# DummyLoad.net
KiCad netlist of a schematic drawn in EAGLE
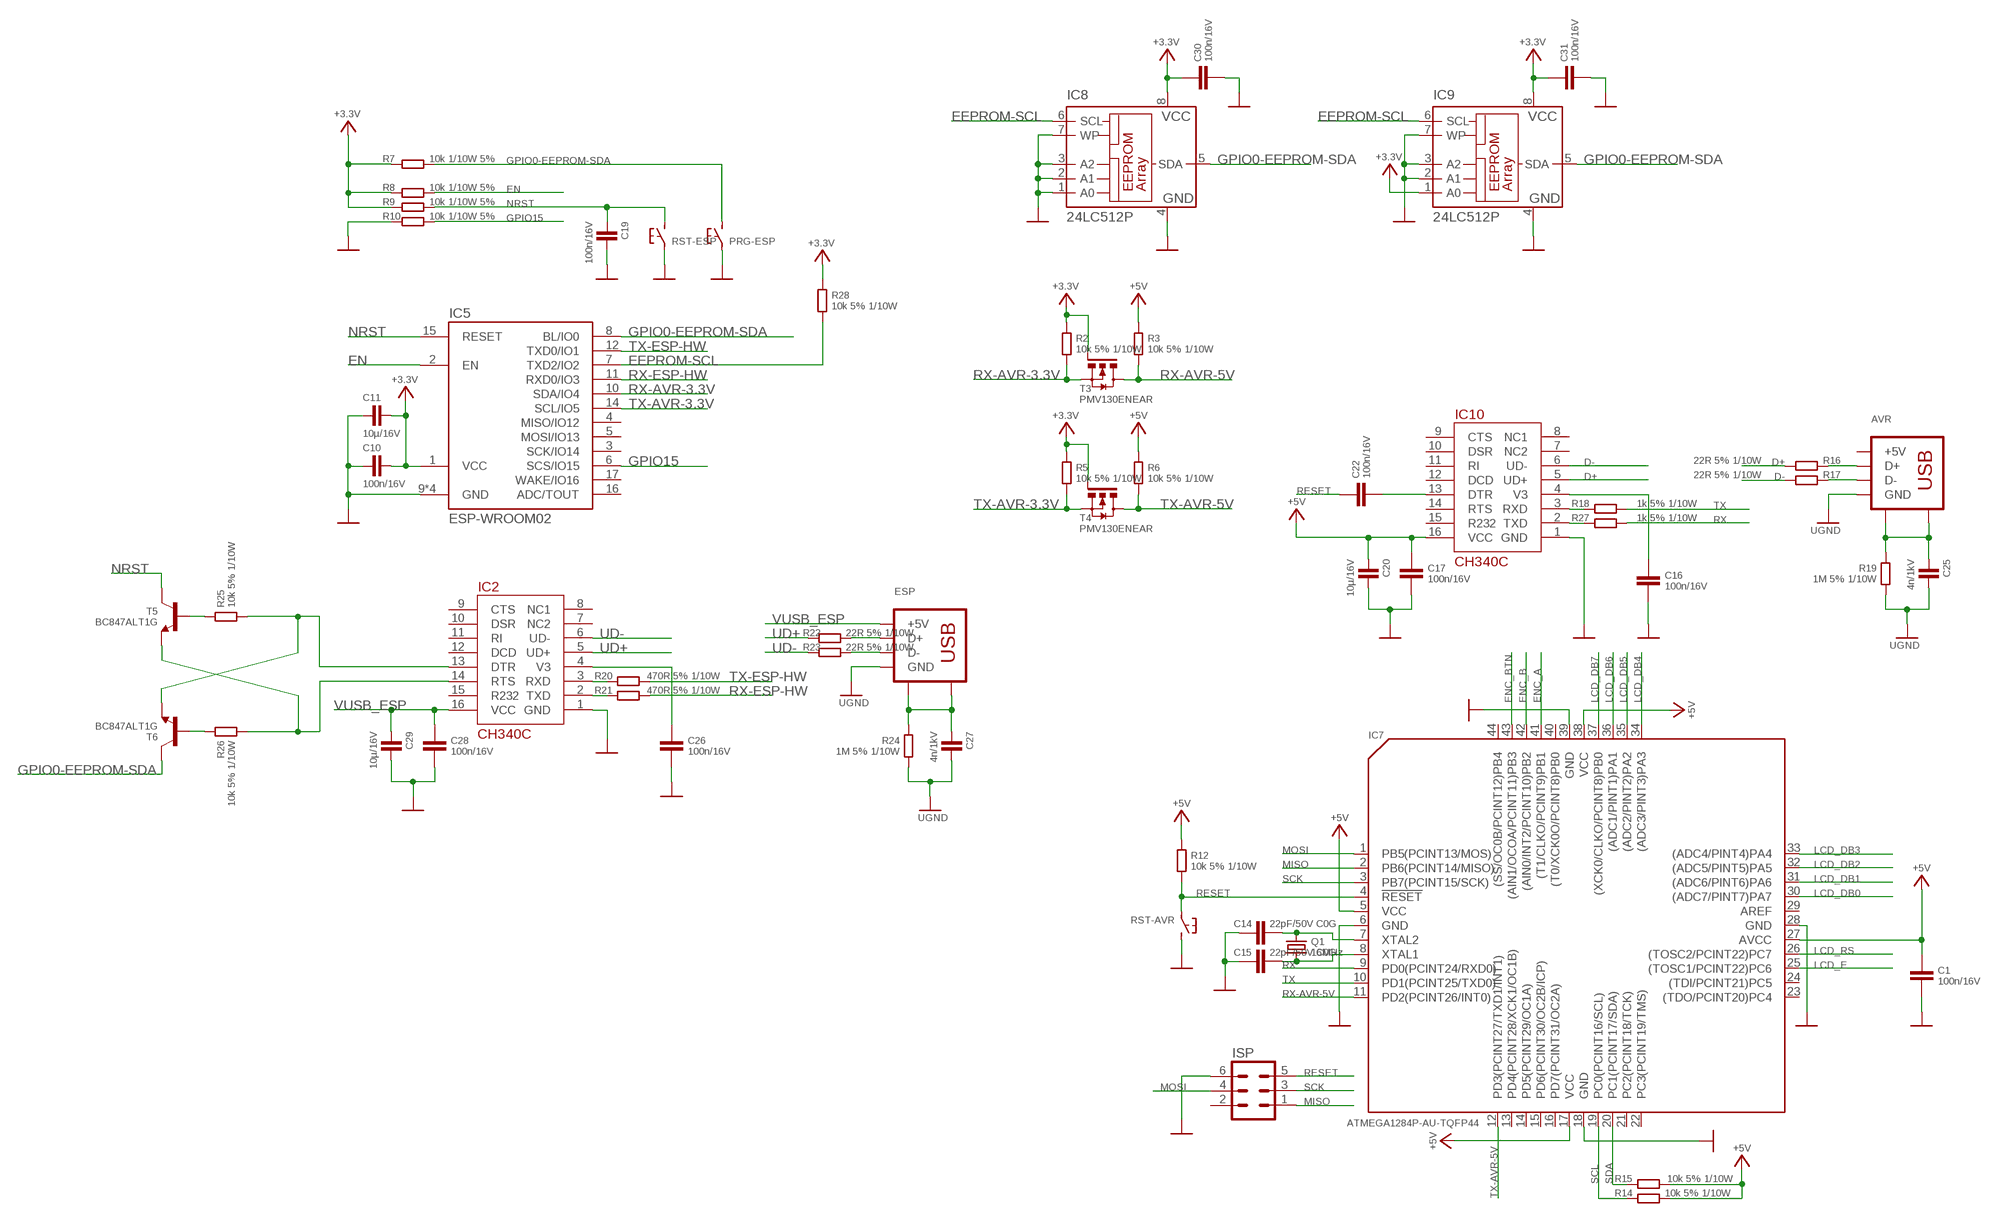
[diagram p0: schematic, sheet 1, part 1 of 2]
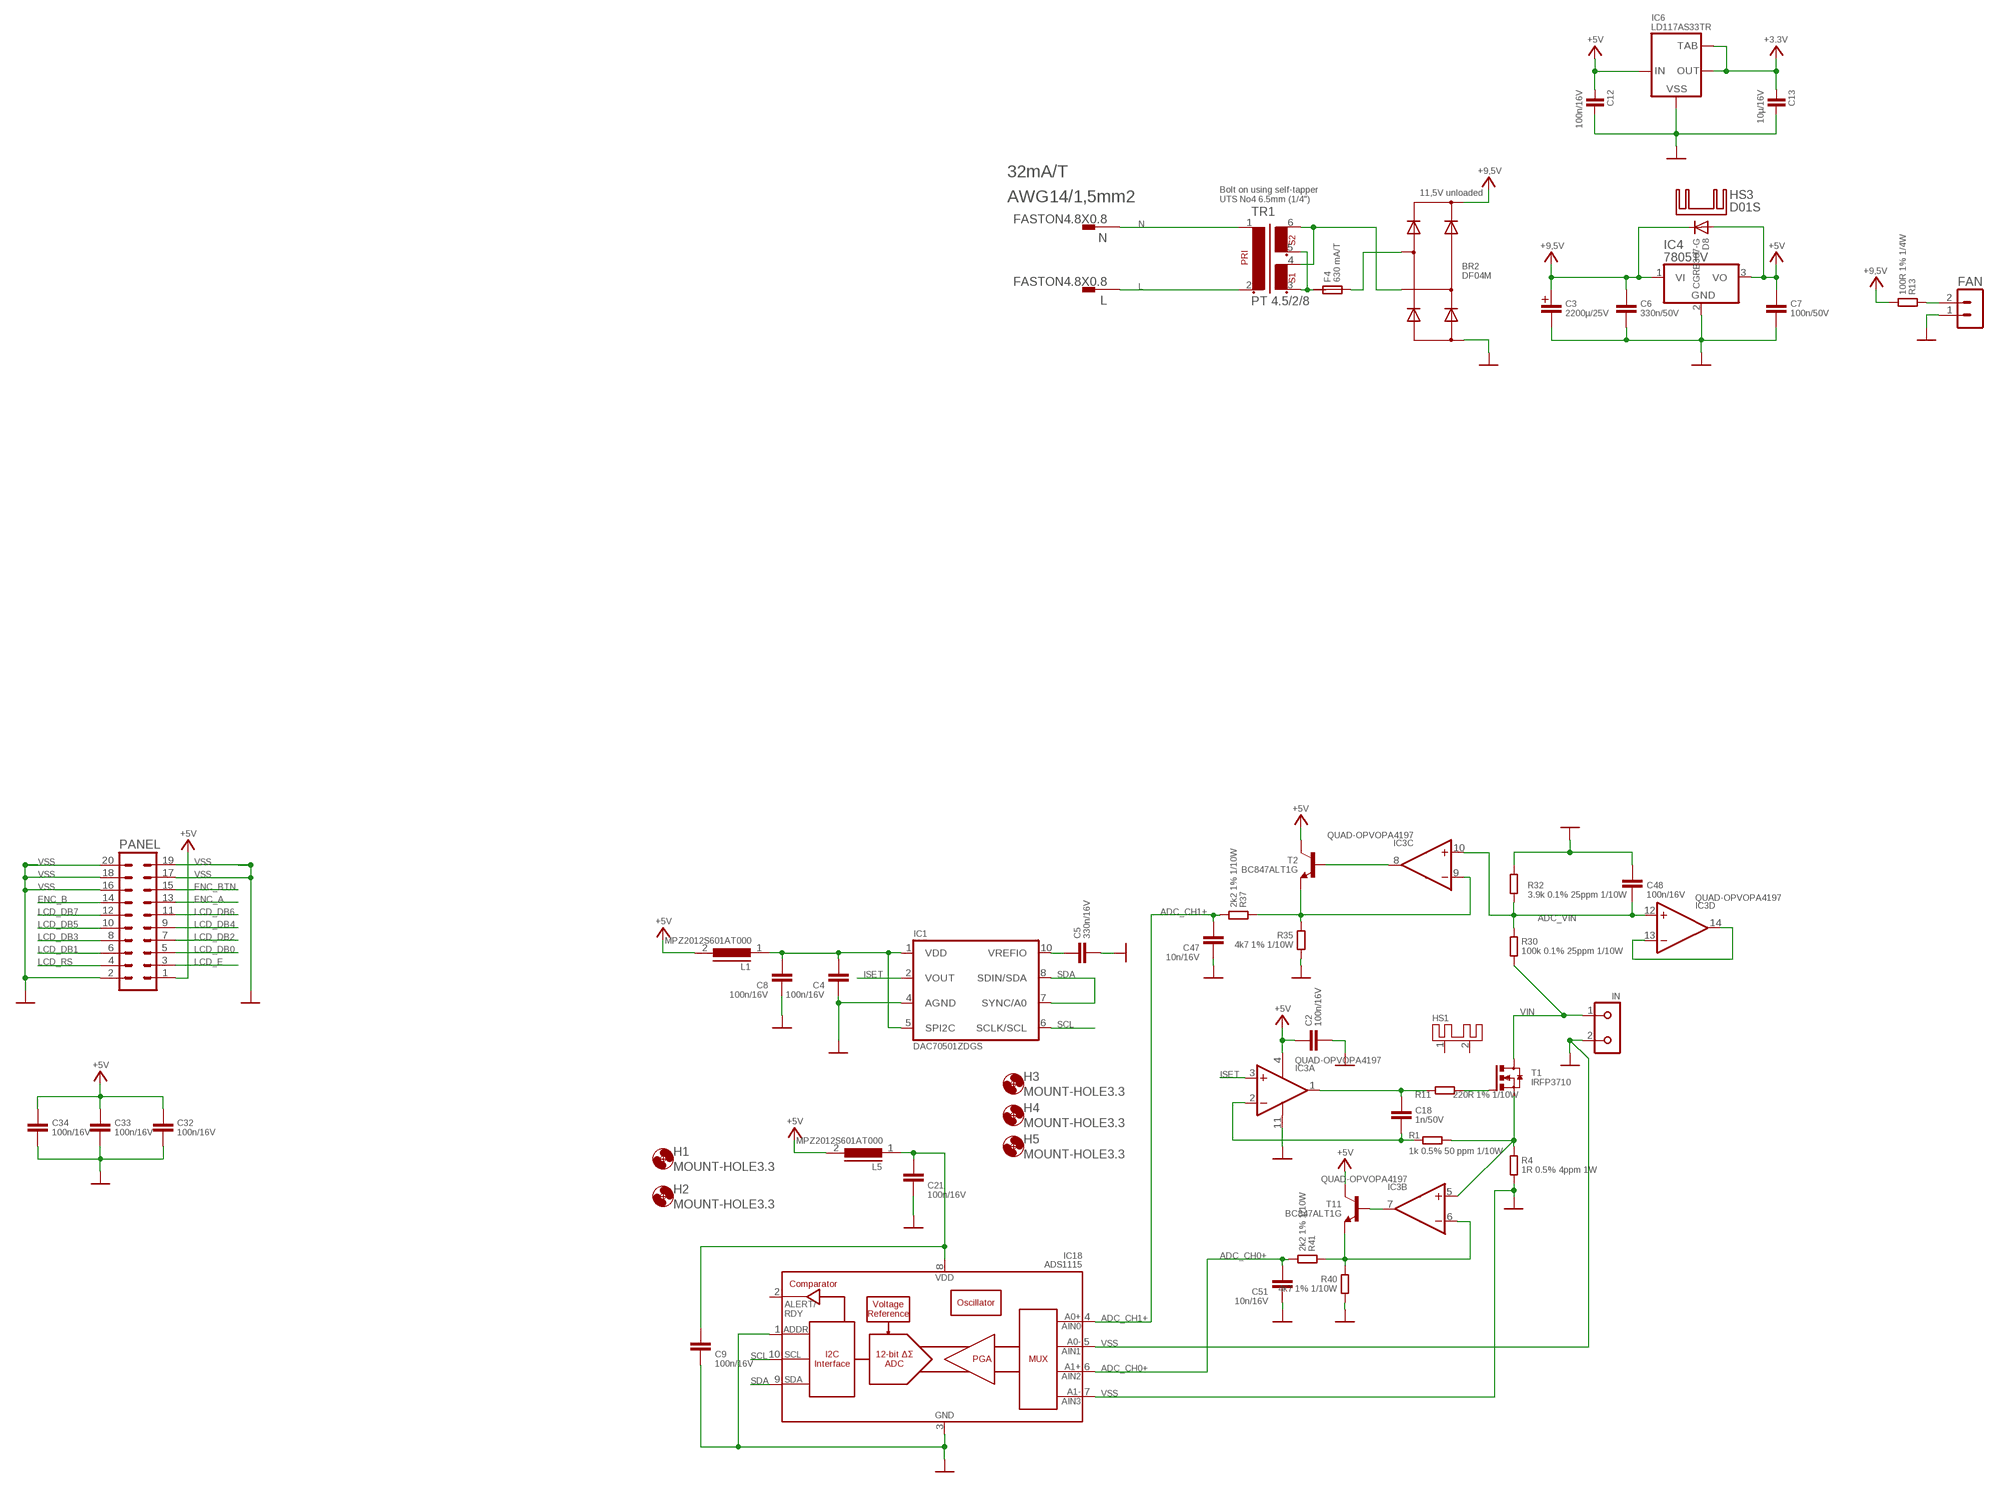
[diagram p1: schematic, sheet 1, part 2 of 2]

(export (version "E")
  (design (tool "Eeschema 10.0.6"))
  (components
    (comp (ref "AVR")
      (value "USBUSB-B")
      (footprint "eagle-import:USB-B")
      (libsource (lib "eagle-import") (part "USBUSB-B"))
    )
    (comp (ref "BR2")
      (value "DF04M")
      (footprint "eagle-import:BR-DIL2")
      (libsource (lib "eagle-import") (part "BRDIL2"))
    )
    (comp (ref "C1")
      (value "100n/16V")
      (footprint "eagle-import:0805")
      (libsource (lib "eagle-import") (part "CC/0805"))
    )
    (comp (ref "C2")
      (value "100n/16V")
      (footprint "eagle-import:0805")
      (libsource (lib "eagle-import") (part "CC/0805"))
    )
    (comp (ref "C3")
      (value "2200µ/25V")
      (footprint "eagle-import:C+_5_12.5")
      (libsource (lib "eagle-import") (part "C+5/12.5"))
    )
    (comp (ref "C4")
      (value "100n/16V")
      (footprint "eagle-import:0805")
      (libsource (lib "eagle-import") (part "CC/0805"))
    )
    (comp (ref "C5")
      (value "330n/16V")
      (footprint "eagle-import:0805")
      (libsource (lib "eagle-import") (part "CC/0805"))
    )
    (comp (ref "C6")
      (value "330n/50V")
      (footprint "eagle-import:0805")
      (libsource (lib "eagle-import") (part "CC/0805"))
    )
    (comp (ref "C7")
      (value "100n/50V")
      (footprint "eagle-import:0805")
      (libsource (lib "eagle-import") (part "CC/0805"))
    )
    (comp (ref "C8")
      (value "100n/16V")
      (footprint "eagle-import:0805")
      (libsource (lib "eagle-import") (part "CC/0805"))
    )
    (comp (ref "C9")
      (value "100n/16V")
      (footprint "eagle-import:0805")
      (libsource (lib "eagle-import") (part "CC/0805"))
    )
    (comp (ref "C10")
      (value "100n/16V")
      (footprint "eagle-import:C0805")
      (libsource (lib "eagle-import") (part "CAPACITOR-0805"))
    )
    (comp (ref "C11")
      (value "10µ/16V")
      (footprint "eagle-import:C1210")
      (libsource (lib "eagle-import") (part "CAPACITOR-1210"))
    )
    (comp (ref "C12")
      (value "100n/16V")
      (footprint "eagle-import:C0805")
      (libsource (lib "eagle-import") (part "CAPACITOR-0805"))
    )
    (comp (ref "C13")
      (value "10µ/16V")
      (footprint "eagle-import:C1210")
      (libsource (lib "eagle-import") (part "CAPACITOR-1210"))
    )
    (comp (ref "C14")
      (value "22pF/50V C0G")
      (footprint "eagle-import:0805")
      (libsource (lib "eagle-import") (part "CC/0805"))
    )
    (comp (ref "C15")
      (value "22pF/50V C0G")
      (footprint "eagle-import:0805")
      (libsource (lib "eagle-import") (part "CC/0805"))
    )
    (comp (ref "C16")
      (value "100n/16V")
      (footprint "eagle-import:0805")
      (libsource (lib "eagle-import") (part "CC/0805"))
    )
    (comp (ref "C17")
      (value "100n/16V")
      (footprint "eagle-import:0805")
      (libsource (lib "eagle-import") (part "CC/0805"))
    )
    (comp (ref "C18")
      (value "1n/50V")
      (footprint "eagle-import:0805")
      (libsource (lib "eagle-import") (part "CC/0805"))
    )
    (comp (ref "C19")
      (value "100n/16V")
      (footprint "eagle-import:C0805")
      (libsource (lib "eagle-import") (part "CAPACITOR-0805"))
    )
    (comp (ref "C20")
      (value "10µ/16V")
      (footprint "eagle-import:C1210")
      (libsource (lib "eagle-import") (part "CAPACITOR-1210"))
    )
    (comp (ref "C21")
      (value "100n/16V")
      (footprint "eagle-import:0805")
      (libsource (lib "eagle-import") (part "CC/0805"))
    )
    (comp (ref "C22")
      (value "100n/16V")
      (footprint "eagle-import:0805")
      (libsource (lib "eagle-import") (part "CC/0805"))
    )
    (comp (ref "C25")
      (value "4n/1kV")
      (footprint "eagle-import:C1206")
      (libsource (lib "eagle-import") (part "CAPACITOR-1206"))
    )
    (comp (ref "C26")
      (value "100n/16V")
      (footprint "eagle-import:0805")
      (libsource (lib "eagle-import") (part "CC/0805"))
    )
    (comp (ref "C27")
      (value "4n/1kV")
      (footprint "eagle-import:C1206")
      (libsource (lib "eagle-import") (part "CAPACITOR-1206"))
    )
    (comp (ref "C28")
      (value "100n/16V")
      (footprint "eagle-import:0805")
      (libsource (lib "eagle-import") (part "CC/0805"))
    )
    (comp (ref "C29")
      (value "10µ/16V")
      (footprint "eagle-import:C1210")
      (libsource (lib "eagle-import") (part "CAPACITOR-1210"))
    )
    (comp (ref "C30")
      (value "100n/16V")
      (footprint "eagle-import:0805")
      (libsource (lib "eagle-import") (part "CC/0805"))
    )
    (comp (ref "C31")
      (value "100n/16V")
      (footprint "eagle-import:0805")
      (libsource (lib "eagle-import") (part "CC/0805"))
    )
    (comp (ref "C32")
      (value "100n/16V")
      (footprint "eagle-import:0805")
      (libsource (lib "eagle-import") (part "CC/0805"))
    )
    (comp (ref "C33")
      (value "100n/16V")
      (footprint "eagle-import:0805")
      (libsource (lib "eagle-import") (part "CC/0805"))
    )
    (comp (ref "C34")
      (value "100n/16V")
      (footprint "eagle-import:0805")
      (libsource (lib "eagle-import") (part "CC/0805"))
    )
    (comp (ref "C47")
      (value "10n/16V")
      (footprint "eagle-import:0805")
      (libsource (lib "eagle-import") (part "CC/0805"))
    )
    (comp (ref "C48")
      (value "100n/16V")
      (footprint "eagle-import:0805")
      (libsource (lib "eagle-import") (part "CC/0805"))
    )
    (comp (ref "C51")
      (value "10n/16V")
      (footprint "eagle-import:0805")
      (libsource (lib "eagle-import") (part "CC/0805"))
    )
    (comp (ref "D8")
      (value "CGRB307-G")
      (footprint "eagle-import:DO214AA-CGRB307-G")
      (libsource (lib "eagle-import") (part "DWIDE"))
    )
    (comp (ref "ESP")
      (value "USBUSB-B")
      (footprint "eagle-import:USB-B")
      (libsource (lib "eagle-import") (part "USBUSB-B"))
    )
    (comp (ref "F4")
      (value "630 mA/T")
      (footprint "eagle-import:F5X20")
      (libsource (lib "eagle-import") (part "F5X20"))
    )
    (comp (ref "FAN")
      (value "JST-PH-2.0-2P")
      (footprint "eagle-import:JST-PH-2.0-2P")
      (libsource (lib "eagle-import") (part "JST-PH-2.0-2P"))
    )
    (comp (ref "H1")
      (value "MOUNT-HOLE3.3")
      (footprint "eagle-import:3,3")
      (libsource (lib "eagle-import") (part "MOUNT-HOLE3.3"))
    )
    (comp (ref "H2")
      (value "MOUNT-HOLE3.3")
      (footprint "eagle-import:3,3")
      (libsource (lib "eagle-import") (part "MOUNT-HOLE3.3"))
    )
    (comp (ref "H3")
      (value "MOUNT-HOLE3.3")
      (footprint "eagle-import:3,3")
      (libsource (lib "eagle-import") (part "MOUNT-HOLE3.3"))
    )
    (comp (ref "H4")
      (value "MOUNT-HOLE3.3")
      (footprint "eagle-import:3,3")
      (libsource (lib "eagle-import") (part "MOUNT-HOLE3.3"))
    )
    (comp (ref "H5")
      (value "MOUNT-HOLE3.3")
      (footprint "eagle-import:3,3")
      (libsource (lib "eagle-import") (part "MOUNT-HOLE3.3"))
    )
    (comp (ref "HS1")
      (value "HSCR201-50")
      (footprint "eagle-import:CR201-50")
      (libsource (lib "eagle-import") (part "HSCR201-50"))
    )
    (comp (ref "HS3")
      (value "D01S")
      (footprint "eagle-import:D01S")
      (libsource (lib "eagle-import") (part "D01S"))
    )
    (comp (ref "IC1")
      (value "DAC70501ZDGS")
      (footprint "eagle-import:VSSOP10")
      (libsource (lib "eagle-import") (part "DAC70501"))
    )
    (comp (ref "IC2")
      (value "CH340C")
      (footprint "eagle-import:SOP16")
      (libsource (lib "eagle-import") (part "CH340C"))
    )
    (comp (ref "IC3")
      (value "QUAD-OPVOPA4197")
      (footprint "eagle-import:SO14")
      (fields (field (name "OC_MOUSER") "595-OPA4197IDR"))
      (libsource (lib "eagle-import") (part "QUAD-OPVOPA4197"))
    )
    (comp (ref "IC4")
      (value "7805TV")
      (footprint "eagle-import:TO220V")
      (libsource (lib "eagle-import") (part "78TV05"))
    )
    (comp (ref "IC5")
      (value "ESP-WROOM02")
      (footprint "eagle-import:ESP-WROOM02")
      (libsource (lib "eagle-import") (part "ESP-WROOM02"))
    )
    (comp (ref "IC6")
      (value "LD117AS33TR")
      (footprint "eagle-import:SOT223")
      (libsource (lib "eagle-import") (part "LD117A?S33TR"))
    )
    (comp (ref "IC7")
      (value "ATMEGA1284P-AU-TQFP44")
      (footprint "eagle-import:TQFP44-0.8-9.6X9.6MM")
      (fields (field (name "MPN") "ATMEGA1284P-AU"))
      (libsource (lib "eagle-import") (part "MCU-ATMEGA1284P-AU(TQFP44)"))
    )
    (comp (ref "IC8")
      (value "24LC512P")
      (footprint "eagle-import:DIL08")
      (libsource (lib "eagle-import") (part "24P"))
    )
    (comp (ref "IC9")
      (value "24LC512P")
      (footprint "eagle-import:DIL08")
      (libsource (lib "eagle-import") (part "24P"))
    )
    (comp (ref "IC10")
      (value "CH340C")
      (footprint "eagle-import:SOP16")
      (libsource (lib "eagle-import") (part "CH340C"))
    )
    (comp (ref "IC18")
      (value "ADS1115")
      (footprint "eagle-import:VSSOP10")
      (libsource (lib "eagle-import") (part "ADS1015VSSOP10"))
    )
    (comp (ref "IN")
      (value "KL2691311500002")
      (footprint "eagle-import:KL2-691311500002")
      (libsource (lib "eagle-import") (part "KL2691311500002"))
    )
    (comp (ref "ISP")
      (value "ML6")
      (footprint "eagle-import:ML6")
      (libsource (lib "eagle-import") (part "ML6"))
    )
    (comp (ref "L")
      (value "FASTON4.8X0.8")
      (footprint "eagle-import:FASTON-4.8X0.8")
      (libsource (lib "eagle-import") (part "FASTON4.8X0.8"))
    )
    (comp (ref "L1")
      (value "MPZ2012S601AT000")
      (footprint "eagle-import:C0805K")
      (libsource (lib "eagle-import") (part "L0805"))
    )
    (comp (ref "L5")
      (value "MPZ2012S601AT000")
      (footprint "eagle-import:C0805K")
      (libsource (lib "eagle-import") (part "L0805"))
    )
    (comp (ref "N")
      (value "FASTON4.8X0.8")
      (footprint "eagle-import:FASTON-4.8X0.8")
      (libsource (lib "eagle-import") (part "FASTON4.8X0.8"))
    )
    (comp (ref "PANEL")
      (value "MA10-2")
      (footprint "eagle-import:MA10-2")
      (libsource (lib "eagle-import") (part "MA10-2"))
    )
    (comp (ref "PRG-ESP")
      (value "TS1B3F-10XX")
      (footprint "eagle-import:B3F-10XX")
      (libsource (lib "eagle-import") (part "TS1B3F-10XX"))
    )
    (comp (ref "Q1")
      (value "16MHz")
      (footprint "eagle-import:Q-5X3.2MM-TXC-7A.SERIES")
      (libsource (lib "eagle-import") (part "Q5X3.2MM-TXC-7A-SERIES"))
    )
    (comp (ref "R1")
      (value "1k 0.5% 50 ppm 1/10W")
      (footprint "eagle-import:C0805K")
      (libsource (lib "eagle-import") (part "R-SMD0805"))
    )
    (comp (ref "R2")
      (value "10k 5% 1/10W")
      (footprint "eagle-import:C0805K")
      (libsource (lib "eagle-import") (part "R-SMD0805"))
    )
    (comp (ref "R3")
      (value "10k 5% 1/10W")
      (footprint "eagle-import:C0805K")
      (libsource (lib "eagle-import") (part "R-SMD0805"))
    )
    (comp (ref "R4")
      (value "1R 0.5% 4ppm 1W")
      (footprint "eagle-import:R-SHUNT-VSR")
      (libsource (lib "eagle-import") (part "R-SHUNTVSR"))
    )
    (comp (ref "R5")
      (value "10k 5% 1/10W")
      (footprint "eagle-import:C0805K")
      (libsource (lib "eagle-import") (part "R-SMD0805"))
    )
    (comp (ref "R6")
      (value "10k 5% 1/10W")
      (footprint "eagle-import:C0805K")
      (libsource (lib "eagle-import") (part "R-SMD0805"))
    )
    (comp (ref "R7")
      (value "10k 1/10W 5%")
      (footprint "eagle-import:C0805K")
      (libsource (lib "eagle-import") (part "R-SMD0805"))
    )
    (comp (ref "R8")
      (value "10k 1/10W 5%")
      (footprint "eagle-import:C0805K")
      (libsource (lib "eagle-import") (part "R-SMD0805"))
    )
    (comp (ref "R9")
      (value "10k 1/10W 5%")
      (footprint "eagle-import:C0805K")
      (libsource (lib "eagle-import") (part "R-SMD0805"))
    )
    (comp (ref "R10")
      (value "10k 1/10W 5%")
      (footprint "eagle-import:C0805K")
      (libsource (lib "eagle-import") (part "R-SMD0805"))
    )
    (comp (ref "R11")
      (value "220R 1% 1/10W")
      (footprint "eagle-import:C0805K")
      (libsource (lib "eagle-import") (part "R-SMD0805"))
    )
    (comp (ref "R12")
      (value "10k 5% 1/10W")
      (footprint "eagle-import:C0805K")
      (libsource (lib "eagle-import") (part "R-SMD0805"))
    )
    (comp (ref "R13")
      (value "100R 1% 1/4W")
      (footprint "eagle-import:C0805K")
      (libsource (lib "eagle-import") (part "R-SMD0805"))
    )
    (comp (ref "R14")
      (value "10k 5% 1/10W")
      (footprint "eagle-import:C0805K")
      (libsource (lib "eagle-import") (part "R-SMD0805"))
    )
    (comp (ref "R15")
      (value "10k 5% 1/10W")
      (footprint "eagle-import:C0805K")
      (libsource (lib "eagle-import") (part "R-SMD0805"))
    )
    (comp (ref "R16")
      (value "22R 5% 1/10W")
      (footprint "eagle-import:C0805K")
      (libsource (lib "eagle-import") (part "R-SMD0805"))
    )
    (comp (ref "R17")
      (value "22R 5% 1/10W")
      (footprint "eagle-import:C0805K")
      (libsource (lib "eagle-import") (part "R-SMD0805"))
    )
    (comp (ref "R18")
      (value "1k 5% 1/10W")
      (footprint "eagle-import:C0805K")
      (libsource (lib "eagle-import") (part "R-SMD0805"))
    )
    (comp (ref "R19")
      (value "1M 5% 1/10W")
      (footprint "eagle-import:C0805K")
      (libsource (lib "eagle-import") (part "R-SMD0805"))
    )
    (comp (ref "R20")
      (value "470R 5% 1/10W")
      (footprint "eagle-import:C0805K")
      (libsource (lib "eagle-import") (part "R-SMD0805"))
    )
    (comp (ref "R21")
      (value "470R 5% 1/10W")
      (footprint "eagle-import:C0805K")
      (libsource (lib "eagle-import") (part "R-SMD0805"))
    )
    (comp (ref "R22")
      (value "22R 5% 1/10W")
      (footprint "eagle-import:C0805K")
      (libsource (lib "eagle-import") (part "R-SMD0805"))
    )
    (comp (ref "R23")
      (value "22R 5% 1/10W")
      (footprint "eagle-import:C0805K")
      (libsource (lib "eagle-import") (part "R-SMD0805"))
    )
    (comp (ref "R24")
      (value "1M 5% 1/10W")
      (footprint "eagle-import:C0805K")
      (libsource (lib "eagle-import") (part "R-SMD0805"))
    )
    (comp (ref "R25")
      (value "10k 5% 1/10W")
      (footprint "eagle-import:C0805K")
      (libsource (lib "eagle-import") (part "R-SMD0805"))
    )
    (comp (ref "R26")
      (value "10k 5% 1/10W")
      (footprint "eagle-import:C0805K")
      (libsource (lib "eagle-import") (part "R-SMD0805"))
    )
    (comp (ref "R27")
      (value "1k 5% 1/10W")
      (footprint "eagle-import:C0805K")
      (libsource (lib "eagle-import") (part "R-SMD0805"))
    )
    (comp (ref "R28")
      (value "10k 5% 1/10W")
      (footprint "eagle-import:C0805K")
      (libsource (lib "eagle-import") (part "R-SMD0805"))
    )
    (comp (ref "R30")
      (value "100k 0.1% 25ppm 1/10W")
      (footprint "eagle-import:C0805K")
      (libsource (lib "eagle-import") (part "R-SMD0805"))
    )
    (comp (ref "R32")
      (value "3.9k 0.1% 25ppm 1/10W")
      (footprint "eagle-import:C0805K")
      (libsource (lib "eagle-import") (part "R-SMD0805"))
    )
    (comp (ref "R35")
      (value "4k7 1% 1/10W")
      (footprint "eagle-import:C0805K")
      (libsource (lib "eagle-import") (part "R-SMD0805"))
    )
    (comp (ref "R37")
      (value "2k2 1% 1/10W")
      (footprint "eagle-import:C0805K")
      (libsource (lib "eagle-import") (part "R-SMD0805"))
    )
    (comp (ref "R40")
      (value "4k7 1% 1/10W")
      (footprint "eagle-import:C0805K")
      (libsource (lib "eagle-import") (part "R-SMD0805"))
    )
    (comp (ref "R41")
      (value "2k2 1% 1/10W")
      (footprint "eagle-import:C0805K")
      (libsource (lib "eagle-import") (part "R-SMD0805"))
    )
    (comp (ref "RST-AVR")
      (value "TS1B3F-10XX")
      (footprint "eagle-import:B3F-10XX")
      (libsource (lib "eagle-import") (part "TS1B3F-10XX"))
    )
    (comp (ref "RST-ESP")
      (value "TS1B3F-10XX")
      (footprint "eagle-import:B3F-10XX")
      (libsource (lib "eagle-import") (part "TS1B3F-10XX"))
    )
    (comp (ref "T1")
      (value "IRFP3710")
      (footprint "eagle-import:TOP3AV")
      (libsource (lib "eagle-import") (part "T-NMOSTO247"))
    )
    (comp (ref "T2")
      (value "BC847ALT1G")
      (footprint "eagle-import:SOT23-BEC")
      (libsource (lib "eagle-import") (part "T-NPNSOT23-BEC"))
    )
    (comp (ref "T3")
      (value "PMV130ENEAR")
      (footprint "eagle-import:SOT23")
      (libsource (lib "eagle-import") (part "T-NMOSIRLML2502PBF"))
    )
    (comp (ref "T4")
      (value "PMV130ENEAR")
      (footprint "eagle-import:SOT23")
      (libsource (lib "eagle-import") (part "T-NMOSIRLML2502PBF"))
    )
    (comp (ref "T5")
      (value "BC847ALT1G")
      (footprint "eagle-import:SOT23-BEC")
      (libsource (lib "eagle-import") (part "T-NPNSOT23-BEC"))
    )
    (comp (ref "T6")
      (value "BC847ALT1G")
      (footprint "eagle-import:SOT23-BEC")
      (libsource (lib "eagle-import") (part "T-NPNSOT23-BEC"))
    )
    (comp (ref "T11")
      (value "BC847ALT1G")
      (footprint "eagle-import:SOT23-BEC")
      (libsource (lib "eagle-import") (part "T-NPNSOT23-BEC"))
    )
    (comp (ref "TR1")
      (value "PT 4.5/2/8")
      (footprint "eagle-import:PT_4,5_2_..")
      (libsource (lib "eagle-import") (part "PT4,5/2/.."))
    )
  )
  (nets
    (net (code "1") (name "+3.3V") (class "Default")
      (node (ref "C10") (pin "2") (pinfunction "2_2") (pintype "passive"))
      (node (ref "C11") (pin "2") (pinfunction "2_2") (pintype "passive"))
      (node (ref "C13") (pin "1") (pinfunction "1_1") (pintype "passive"))
      (node (ref "C30") (pin "1") (pinfunction "1_1") (pintype "passive"))
      (node (ref "C31") (pin "1") (pinfunction "1_1") (pintype "passive"))
      (node (ref "IC5") (pin "1") (pinfunction "VCC_1") (pintype "power_in"))
      (node (ref "IC6") (pin "2") (pinfunction "OUT_2") (pintype "passive"))
      (node (ref "IC6") (pin "4") (pinfunction "OUT1_4") (pintype "passive"))
      (node (ref "IC8") (pin "8") (pinfunction "VCC_8") (pintype "power_in"))
      (node (ref "IC9") (pin "1") (pinfunction "A0_1") (pintype "input"))
      (node (ref "IC9") (pin "8") (pinfunction "VCC_8") (pintype "power_in"))
      (node (ref "R2") (pin "1") (pinfunction "1_1") (pintype "passive"))
      (node (ref "R28") (pin "1") (pinfunction "1_1") (pintype "passive"))
      (node (ref "R5") (pin "1") (pinfunction "1_1") (pintype "passive"))
      (node (ref "R7") (pin "1") (pinfunction "1_1") (pintype "passive"))
      (node (ref "R8") (pin "1") (pinfunction "1_1") (pintype "passive"))
      (node (ref "R9") (pin "1") (pinfunction "1_1") (pintype "passive"))
      (node (ref "T3") (pin "1") (pinfunction "G_1") (pintype "passive"))
      (node (ref "T4") (pin "1") (pinfunction "G_1") (pintype "passive"))
    )
    (net (code "2") (name "+5V") (class "Default")
      (node (ref "C1") (pin "1") (pinfunction "1_1") (pintype "passive"))
      (node (ref "C12") (pin "1") (pinfunction "1_1") (pintype "passive"))
      (node (ref "C17") (pin "1") (pinfunction "1_1") (pintype "passive"))
      (node (ref "C2") (pin "1") (pinfunction "1_1") (pintype "passive"))
      (node (ref "C20") (pin "1") (pinfunction "1_1") (pintype "passive"))
      (node (ref "C32") (pin "1") (pinfunction "1_1") (pintype "passive"))
      (node (ref "C33") (pin "1") (pinfunction "1_1") (pintype "passive"))
      (node (ref "C34") (pin "1") (pinfunction "1_1") (pintype "passive"))
      (node (ref "C7") (pin "1") (pinfunction "1_1") (pintype "passive"))
      (node (ref "D8") (pin "A") (pinfunction "A_A") (pintype "passive"))
      (node (ref "IC10") (pin "16") (pinfunction "VCC_16") (pintype "power_in"))
      (node (ref "IC3") (pin "4") (pinfunction "V+_4") (pintype "power_in"))
      (node (ref "IC4") (pin "3") (pinfunction "VO_3") (pintype "passive"))
      (node (ref "IC6") (pin "3") (pinfunction "IN_3") (pintype "input"))
      (node (ref "IC7") (pin "17") (pinfunction "VCC_17") (pintype "bidirectional"))
      (node (ref "IC7") (pin "27") (pinfunction "AVCC_27") (pintype "bidirectional"))
      (node (ref "IC7") (pin "38") (pinfunction "VCC_38") (pintype "bidirectional"))
      (node (ref "IC7") (pin "5") (pinfunction "VCC_5") (pintype "bidirectional"))
      (node (ref "L1") (pin "2") (pinfunction "2_2") (pintype "passive"))
      (node (ref "L5") (pin "2") (pinfunction "2_2") (pintype "passive"))
      (node (ref "PANEL") (pin "1") (pinfunction "1_1") (pintype "passive"))
      (node (ref "R12") (pin "1") (pinfunction "1_1") (pintype "passive"))
      (node (ref "R14") (pin "2") (pinfunction "2_2") (pintype "passive"))
      (node (ref "R15") (pin "2") (pinfunction "2_2") (pintype "passive"))
      (node (ref "R3") (pin "1") (pinfunction "1_1") (pintype "passive"))
      (node (ref "R6") (pin "1") (pinfunction "1_1") (pintype "passive"))
      (node (ref "T11") (pin "C") (pinfunction "C_C") (pintype "passive"))
      (node (ref "T2") (pin "C") (pinfunction "C_C") (pintype "passive"))
    )
    (net (code "3") (name "+9,5V") (class "Default")
      (node (ref "BR2") (pin "DC+") (pinfunction "DC+_DC+") (pintype "passive"))
      (node (ref "C3") (pin "+") (pinfunction "+_+") (pintype "passive"))
      (node (ref "C6") (pin "1") (pinfunction "1_1") (pintype "passive"))
      (node (ref "D8") (pin "C") (pinfunction "C_C") (pintype "passive"))
      (node (ref "IC4") (pin "1") (pinfunction "VI_1") (pintype "input"))
      (node (ref "R13") (pin "2") (pinfunction "2_2") (pintype "passive"))
    )
    (net (code "4") (name "/ADC_CH0+") (class "Default")
      (node (ref "C51") (pin "1") (pinfunction "1_1") (pintype "passive"))
      (node (ref "IC18") (pin "6") (pinfunction "AIN2_6") (pintype "bidirectional"))
      (node (ref "R41") (pin "2") (pinfunction "2_2") (pintype "passive"))
    )
    (net (code "5") (name "/ADC_CH1+") (class "Default")
      (node (ref "C47") (pin "1") (pinfunction "1_1") (pintype "passive"))
      (node (ref "IC18") (pin "4") (pinfunction "AIN0_4") (pintype "bidirectional"))
      (node (ref "R37") (pin "2") (pinfunction "2_2") (pintype "passive"))
    )
    (net (code "6") (name "/ADC_VIN") (class "Default")
      (node (ref "C48") (pin "2") (pinfunction "2_2") (pintype "passive"))
      (node (ref "IC3") (pin "10") (pinfunction "+IN_10") (pintype "input"))
      (node (ref "IC3") (pin "12") (pinfunction "+IN_12") (pintype "input"))
      (node (ref "R30") (pin "1") (pinfunction "1_1") (pintype "passive"))
      (node (ref "R32") (pin "2") (pinfunction "2_2") (pintype "passive"))
    )
    (net (code "7") (name "/D+") (class "Default")
      (node (ref "IC10") (pin "5") (pinfunction "UD+_5") (pintype "bidirectional"))
      (node (ref "R16") (pin "1") (pinfunction "1_1") (pintype "passive"))
    )
    (net (code "8") (name "/D-") (class "Default")
      (node (ref "IC10") (pin "6") (pinfunction "UD-_6") (pintype "bidirectional"))
      (node (ref "R17") (pin "1") (pinfunction "1_1") (pintype "passive"))
    )
    (net (code "9") (name "/EEPROM-SCL") (class "Default")
      (node (ref "IC5") (pin "7") (pinfunction "TXD2/IO2_7") (pintype "bidirectional"))
      (node (ref "IC8") (pin "6") (pinfunction "SCL_6") (pintype "input"))
      (node (ref "IC9") (pin "6") (pinfunction "SCL_6") (pintype "input"))
      (node (ref "R28") (pin "2") (pinfunction "2_2") (pintype "passive"))
    )
    (net (code "10") (name "/EN") (class "Default")
      (node (ref "IC5") (pin "2") (pinfunction "EN_2") (pintype "bidirectional"))
      (node (ref "R8") (pin "2") (pinfunction "2_2") (pintype "passive"))
    )
    (net (code "11") (name "/ENC_A") (class "Default")
      (node (ref "IC7") (pin "41") (pinfunction "(T1/CLKO/PCINT9)PB1_41") (pintype "bidirectional"))
      (node (ref "PANEL") (pin "13") (pinfunction "13_13") (pintype "passive"))
    )
    (net (code "12") (name "/ENC_B") (class "Default")
      (node (ref "IC7") (pin "42") (pinfunction "(AIN0/INT2/PCINT10)PB2_42") (pintype "bidirectional"))
      (node (ref "PANEL") (pin "14") (pinfunction "14_14") (pintype "passive"))
    )
    (net (code "13") (name "/ENC_BTN") (class "Default")
      (node (ref "IC7") (pin "43") (pinfunction "(AIN1/OCOA/PCINT11)PB3_43") (pintype "bidirectional"))
      (node (ref "PANEL") (pin "15") (pinfunction "15_15") (pintype "passive"))
    )
    (net (code "14") (name "/GPIO0-EEPROM-SDA") (class "Default")
      (node (ref "IC5") (pin "8") (pinfunction "BL/IO0_8") (pintype "bidirectional"))
      (node (ref "IC8") (pin "5") (pinfunction "SDA_5") (pintype "bidirectional"))
      (node (ref "IC9") (pin "5") (pinfunction "SDA_5") (pintype "bidirectional"))
      (node (ref "PRG-ESP") (pin "3") (pinfunction "2_3") (pintype "passive"))
      (node (ref "R7") (pin "2") (pinfunction "2_2") (pintype "passive"))
      (node (ref "T6") (pin "C") (pinfunction "C_C") (pintype "passive"))
    )
    (net (code "15") (name "/GPIO15") (class "Default")
      (node (ref "IC5") (pin "6") (pinfunction "SCS/IO15_6") (pintype "bidirectional"))
      (node (ref "R10") (pin "2") (pinfunction "2_2") (pintype "passive"))
    )
    (net (code "16") (name "/ISET") (class "Default")
      (node (ref "IC1") (pin "2") (pinfunction "VOUT_2") (pintype "output"))
      (node (ref "IC3") (pin "3") (pinfunction "+IN_3") (pintype "input"))
    )
    (net (code "17") (name "/L") (class "Default")
      (node (ref "L") (pin "A1") (pinfunction "1_A1") (pintype "passive"))
      (node (ref "L") (pin "A2") (pinfunction "1_A2") (pintype "passive"))
      (node (ref "TR1") (pin "2") (pinfunction "2_2") (pintype "passive"))
    )
    (net (code "18") (name "/LCD_DB0") (class "Default")
      (node (ref "IC7") (pin "30") (pinfunction "(ADC7/PINT7)PA7_30") (pintype "bidirectional"))
      (node (ref "PANEL") (pin "5") (pinfunction "5_5") (pintype "passive"))
    )
    (net (code "19") (name "/LCD_DB1") (class "Default")
      (node (ref "IC7") (pin "31") (pinfunction "(ADC6/PINT6)PA6_31") (pintype "bidirectional"))
      (node (ref "PANEL") (pin "6") (pinfunction "6_6") (pintype "passive"))
    )
    (net (code "20") (name "/LCD_DB2") (class "Default")
      (node (ref "IC7") (pin "32") (pinfunction "(ADC5/PINT5)PA5_32") (pintype "bidirectional"))
      (node (ref "PANEL") (pin "7") (pinfunction "7_7") (pintype "passive"))
    )
    (net (code "21") (name "/LCD_DB3") (class "Default")
      (node (ref "IC7") (pin "33") (pinfunction "(ADC4/PINT4)PA4_33") (pintype "bidirectional"))
      (node (ref "PANEL") (pin "8") (pinfunction "8_8") (pintype "passive"))
    )
    (net (code "22") (name "/LCD_DB4") (class "Default")
      (node (ref "IC7") (pin "34") (pinfunction "(ADC3/PINT3)PA3_34") (pintype "bidirectional"))
      (node (ref "PANEL") (pin "9") (pinfunction "9_9") (pintype "passive"))
    )
    (net (code "23") (name "/LCD_DB5") (class "Default")
      (node (ref "IC7") (pin "35") (pinfunction "(ADC2/PINT2)PA2_35") (pintype "bidirectional"))
      (node (ref "PANEL") (pin "10") (pinfunction "10_10") (pintype "passive"))
    )
    (net (code "24") (name "/LCD_DB6") (class "Default")
      (node (ref "IC7") (pin "36") (pinfunction "(ADC1/PINT1)PA1_36") (pintype "bidirectional"))
      (node (ref "PANEL") (pin "11") (pinfunction "11_11") (pintype "passive"))
    )
    (net (code "25") (name "/LCD_DB7") (class "Default")
      (node (ref "IC7") (pin "37") (pinfunction "(XCK0/CLKO/PCINT8)PB0_37") (pintype "bidirectional"))
      (node (ref "PANEL") (pin "12") (pinfunction "12_12") (pintype "passive"))
    )
    (net (code "26") (name "/LCD_E") (class "Default")
      (node (ref "IC7") (pin "25") (pinfunction "(TOSC1/PCINT22)PC6_25") (pintype "bidirectional"))
      (node (ref "PANEL") (pin "3") (pinfunction "3_3") (pintype "passive"))
    )
    (net (code "27") (name "/LCD_RS") (class "Default")
      (node (ref "IC7") (pin "26") (pinfunction "(TOSC2/PCINT22)PC7_26") (pintype "bidirectional"))
      (node (ref "PANEL") (pin "4") (pinfunction "4_4") (pintype "passive"))
    )
    (net (code "28") (name "/MISO") (class "Default")
      (node (ref "IC7") (pin "2") (pinfunction "PB6(PCINT14/MISO)_2") (pintype "bidirectional"))
      (node (ref "ISP") (pin "1") (pinfunction "1_1") (pintype "passive"))
    )
    (net (code "29") (name "/MOSI") (class "Default")
      (node (ref "IC7") (pin "1") (pinfunction "PB5(PCINT13/MOS)_1") (pintype "bidirectional"))
      (node (ref "ISP") (pin "4") (pinfunction "4_4") (pintype "passive"))
    )
    (net (code "30") (name "/N") (class "Default")
      (node (ref "N") (pin "A1") (pinfunction "1_A1") (pintype "passive"))
      (node (ref "N") (pin "A2") (pinfunction "1_A2") (pintype "passive"))
      (node (ref "TR1") (pin "1") (pinfunction "1_1") (pintype "passive"))
    )
    (net (code "31") (name "/NRST") (class "Default")
      (node (ref "C19") (pin "1") (pinfunction "1_1") (pintype "passive"))
      (node (ref "IC5") (pin "15") (pinfunction "RESET_15") (pintype "bidirectional"))
      (node (ref "R9") (pin "2") (pinfunction "2_2") (pintype "passive"))
      (node (ref "RST-ESP") (pin "3") (pinfunction "2_3") (pintype "passive"))
      (node (ref "T5") (pin "C") (pinfunction "C_C") (pintype "passive"))
    )
    (net (code "32") (name "/RESET") (class "Default")
      (node (ref "C22") (pin "1") (pinfunction "1_1") (pintype "passive"))
      (node (ref "IC7") (pin "4") (pinfunction "~{RESET}_4") (pintype "bidirectional"))
      (node (ref "ISP") (pin "5") (pinfunction "5_5") (pintype "passive"))
      (node (ref "R12") (pin "2") (pinfunction "2_2") (pintype "passive"))
      (node (ref "RST-AVR") (pin "1") (pinfunction "1_1") (pintype "passive"))
    )
    (net (code "33") (name "/RX") (class "Default")
      (node (ref "IC7") (pin "9") (pinfunction "PD0(PCINT24/RXD0)_9") (pintype "bidirectional"))
      (node (ref "R27") (pin "2") (pinfunction "2_2") (pintype "passive"))
    )
    (net (code "34") (name "/RX-AVR-3.3V") (class "Default")
      (node (ref "IC5") (pin "10") (pinfunction "SDA/IO4_10") (pintype "bidirectional"))
      (node (ref "R2") (pin "2") (pinfunction "2_2") (pintype "passive"))
      (node (ref "T3") (pin "2") (pinfunction "S_2") (pintype "passive"))
    )
    (net (code "35") (name "/RX-AVR-5V") (class "Default")
      (node (ref "IC7") (pin "11") (pinfunction "PD2(PCINT26/INT0)_11") (pintype "bidirectional"))
      (node (ref "R3") (pin "2") (pinfunction "2_2") (pintype "passive"))
      (node (ref "T3") (pin "3") (pinfunction "D_3") (pintype "passive"))
    )
    (net (code "36") (name "/RX-ESP-HW") (class "Default")
      (node (ref "IC5") (pin "11") (pinfunction "RXD0/IO3_11") (pintype "bidirectional"))
      (node (ref "R21") (pin "2") (pinfunction "2_2") (pintype "passive"))
    )
    (net (code "37") (name "/SCK") (class "Default")
      (node (ref "IC7") (pin "3") (pinfunction "PB7(PCINT15/SCK)_3") (pintype "bidirectional"))
      (node (ref "ISP") (pin "3") (pinfunction "3_3") (pintype "passive"))
    )
    (net (code "38") (name "/SCL") (class "Default")
      (node (ref "IC1") (pin "6") (pinfunction "SCLK/SCL_6") (pintype "input"))
      (node (ref "IC18") (pin "10") (pinfunction "SCL_10") (pintype "bidirectional"))
      (node (ref "IC7") (pin "19") (pinfunction "PC0(PCINT16/SCL)_19") (pintype "bidirectional"))
      (node (ref "R14") (pin "1") (pinfunction "1_1") (pintype "passive"))
    )
    (net (code "39") (name "/SDA") (class "Default")
      (node (ref "IC1") (pin "7") (pinfunction "SYNC/A0_7") (pintype "input"))
      (node (ref "IC1") (pin "8") (pinfunction "SDIN/SDA_8") (pintype "input"))
      (node (ref "IC18") (pin "9") (pinfunction "SDA_9") (pintype "bidirectional"))
      (node (ref "IC7") (pin "20") (pinfunction "PC1(PCINT17/SDA)_20") (pintype "bidirectional"))
      (node (ref "R15") (pin "1") (pinfunction "1_1") (pintype "passive"))
    )
    (net (code "40") (name "/TX") (class "Default")
      (node (ref "IC7") (pin "10") (pinfunction "PD1(PCINT25/TXD0)_10") (pintype "bidirectional"))
      (node (ref "R18") (pin "2") (pinfunction "2_2") (pintype "passive"))
    )
    (net (code "41") (name "/TX-AVR-3.3V") (class "Default")
      (node (ref "IC5") (pin "14") (pinfunction "SCL/IO5_14") (pintype "bidirectional"))
      (node (ref "R5") (pin "2") (pinfunction "2_2") (pintype "passive"))
      (node (ref "T4") (pin "2") (pinfunction "S_2") (pintype "passive"))
    )
    (net (code "42") (name "/TX-AVR-5V") (class "Default")
      (node (ref "IC7") (pin "12") (pinfunction "PD3(PCINT27/TXD1/INT1)_12") (pintype "bidirectional"))
      (node (ref "R6") (pin "2") (pinfunction "2_2") (pintype "passive"))
      (node (ref "T4") (pin "3") (pinfunction "D_3") (pintype "passive"))
    )
    (net (code "43") (name "/TX-ESP-HW") (class "Default")
      (node (ref "IC5") (pin "12") (pinfunction "TXD0/IO1_12") (pintype "bidirectional"))
      (node (ref "R20") (pin "2") (pinfunction "2_2") (pintype "passive"))
    )
    (net (code "44") (name "/UD+") (class "Default")
      (node (ref "IC2") (pin "5") (pinfunction "UD+_5") (pintype "bidirectional"))
      (node (ref "R22") (pin "1") (pinfunction "1_1") (pintype "passive"))
    )
    (net (code "45") (name "/UD-") (class "Default")
      (node (ref "IC2") (pin "6") (pinfunction "UD-_6") (pintype "bidirectional"))
      (node (ref "R23") (pin "1") (pinfunction "1_1") (pintype "passive"))
    )
    (net (code "46") (name "/VIN") (class "Default")
      (node (ref "IN") (pin "1") (pinfunction "1_1") (pintype "passive"))
      (node (ref "R30") (pin "2") (pinfunction "2_2") (pintype "passive"))
      (node (ref "T1") (pin "C") (pinfunction "D_C") (pintype "passive"))
    )
    (net (code "47") (name "/VUSB_ESP") (class "Default")
      (node (ref "C28") (pin "1") (pinfunction "1_1") (pintype "passive"))
      (node (ref "C29") (pin "1") (pinfunction "1_1") (pintype "passive"))
      (node (ref "ESP") (pin "+5V") (pinfunction "+5V_+5V") (pintype "passive"))
      (node (ref "IC2") (pin "16") (pinfunction "VCC_16") (pintype "power_in"))
    )
    (net (code "48") (name "Net-(AVR-PadD+)") (class "Default")
      (node (ref "AVR") (pin "D+") (pinfunction "D+_D+") (pintype "bidirectional"))
      (node (ref "R16") (pin "2") (pinfunction "2_2") (pintype "passive"))
    )
    (net (code "49") (name "Net-(AVR-PadD-)") (class "Default")
      (node (ref "AVR") (pin "D-") (pinfunction "D-_D-") (pintype "bidirectional"))
      (node (ref "R17") (pin "2") (pinfunction "2_2") (pintype "passive"))
    )
    (net (code "50") (name "Net-(AVR-PadSH1)") (class "Default")
      (node (ref "AVR") (pin "SH1") (pinfunction "SH1_SH1") (pintype "passive"))
      (node (ref "AVR") (pin "SH2") (pinfunction "SH2_SH2") (pintype "passive"))
      (node (ref "C25") (pin "1") (pinfunction "1_1") (pintype "passive"))
      (node (ref "R19") (pin "1") (pinfunction "1_1") (pintype "passive"))
    )
    (net (code "51") (name "Net-(BR2-PadAC1)") (class "Default")
      (node (ref "BR2") (pin "AC1") (pinfunction "AC1_AC1") (pintype "passive"))
      (node (ref "F4") (pin "3") (pinfunction "2_3") (pintype "passive"))
      (node (ref "F4") (pin "4") (pinfunction "2_4") (pintype "passive"))
    )
    (net (code "52") (name "Net-(BR2-PadAC2)") (class "Default")
      (node (ref "BR2") (pin "AC2") (pinfunction "AC2_AC2") (pintype "passive"))
      (node (ref "TR1") (pin "4") (pinfunction "4_4") (pintype "passive"))
      (node (ref "TR1") (pin "6") (pinfunction "6_6") (pintype "passive"))
    )
    (net (code "53") (name "Net-(C27-Pad1)") (class "Default")
      (node (ref "C27") (pin "1") (pinfunction "1_1") (pintype "passive"))
      (node (ref "ESP") (pin "SH1") (pinfunction "SH1_SH1") (pintype "passive"))
      (node (ref "ESP") (pin "SH2") (pinfunction "SH2_SH2") (pintype "passive"))
      (node (ref "R24") (pin "1") (pinfunction "1_1") (pintype "passive"))
    )
    (net (code "54") (name "Net-(ESP-PadD+)") (class "Default")
      (node (ref "ESP") (pin "D+") (pinfunction "D+_D+") (pintype "bidirectional"))
      (node (ref "R22") (pin "2") (pinfunction "2_2") (pintype "passive"))
    )
    (net (code "55") (name "Net-(ESP-PadD-)") (class "Default")
      (node (ref "ESP") (pin "D-") (pinfunction "D-_D-") (pintype "bidirectional"))
      (node (ref "R23") (pin "2") (pinfunction "2_2") (pintype "passive"))
    )
    (net (code "56") (name "Net-(F4-1-Pad2)") (class "Default")
      (node (ref "F4") (pin "1") (pinfunction "1_1") (pintype "passive"))
      (node (ref "F4") (pin "2") (pinfunction "1_2") (pintype "passive"))
      (node (ref "TR1") (pin "3") (pinfunction "3_3") (pintype "passive"))
      (node (ref "TR1") (pin "5") (pinfunction "5_5") (pintype "passive"))
    )
    (net (code "57") (name "Net-(FAN-Pad2)") (class "Default")
      (node (ref "FAN") (pin "2") (pinfunction "2_2") (pintype "passive"))
      (node (ref "R13") (pin "1") (pinfunction "1_1") (pintype "passive"))
    )
    (net (code "58") (name "Net-(IC1-SPI2C)") (class "Default")
      (node (ref "C4") (pin "1") (pinfunction "1_1") (pintype "passive"))
      (node (ref "C8") (pin "1") (pinfunction "1_1") (pintype "passive"))
      (node (ref "IC1") (pin "1") (pinfunction "VDD_1") (pintype "power_in"))
      (node (ref "IC1") (pin "5") (pinfunction "SPI2C_5") (pintype "bidirectional"))
      (node (ref "L1") (pin "1") (pinfunction "1_1") (pintype "passive"))
    )
    (net (code "59") (name "Net-(IC1-VREFIO)") (class "Default")
      (node (ref "C5") (pin "1") (pinfunction "1_1") (pintype "passive"))
      (node (ref "IC1") (pin "10") (pinfunction "VREFIO_10") (pintype "bidirectional"))
    )
    (net (code "60") (name "Net-(IC2-DTR)") (class "Default")
      (node (ref "IC2") (pin "13") (pinfunction "DTR_13") (pintype "bidirectional"))
      (node (ref "R25") (pin "2") (pinfunction "2_2") (pintype "passive"))
      (node (ref "T6") (pin "E") (pinfunction "E_E") (pintype "passive"))
    )
    (net (code "61") (name "Net-(IC2-RTS)") (class "Default")
      (node (ref "IC2") (pin "14") (pinfunction "RTS_14") (pintype "bidirectional"))
      (node (ref "R26") (pin "2") (pinfunction "2_2") (pintype "passive"))
      (node (ref "T5") (pin "E") (pinfunction "E_E") (pintype "passive"))
    )
    (net (code "62") (name "Net-(IC2-RXD)") (class "Default")
      (node (ref "IC2") (pin "3") (pinfunction "RXD_3") (pintype "bidirectional"))
      (node (ref "R20") (pin "1") (pinfunction "1_1") (pintype "passive"))
    )
    (net (code "63") (name "Net-(IC2-TXD)") (class "Default")
      (node (ref "IC2") (pin "2") (pinfunction "TXD_2") (pintype "bidirectional"))
      (node (ref "R21") (pin "1") (pinfunction "1_1") (pintype "passive"))
    )
    (net (code "64") (name "Net-(IC2-V3)") (class "Default")
      (node (ref "C26") (pin "1") (pinfunction "1_1") (pintype "passive"))
      (node (ref "IC2") (pin "4") (pinfunction "V3_4") (pintype "bidirectional"))
    )
    (net (code "65") (name "Net-(IC3A--IN)") (class "Default")
      (node (ref "C18") (pin "2") (pinfunction "2_2") (pintype "passive"))
      (node (ref "IC3") (pin "2") (pinfunction "-IN_2") (pintype "input"))
      (node (ref "R1") (pin "2") (pinfunction "2_2") (pintype "passive"))
    )
    (net (code "66") (name "Net-(IC3A-OUT)") (class "Default")
      (node (ref "C18") (pin "1") (pinfunction "1_1") (pintype "passive"))
      (node (ref "IC3") (pin "1") (pinfunction "OUT_1") (pintype "output"))
      (node (ref "R11") (pin "1") (pinfunction "1_1") (pintype "passive"))
    )
    (net (code "67") (name "Net-(IC3B-+IN)") (class "Default")
      (node (ref "IC3") (pin "5") (pinfunction "+IN_5") (pintype "input"))
      (node (ref "R1") (pin "1") (pinfunction "1_1") (pintype "passive"))
      (node (ref "R4") (pin "1") (pinfunction "1_1") (pintype "passive"))
      (node (ref "T1") (pin "E") (pinfunction "S_E") (pintype "passive"))
    )
    (net (code "68") (name "Net-(IC3B--IN)") (class "Default")
      (node (ref "IC3") (pin "6") (pinfunction "-IN_6") (pintype "input"))
      (node (ref "R40") (pin "1") (pinfunction "1_1") (pintype "passive"))
      (node (ref "R41") (pin "1") (pinfunction "1_1") (pintype "passive"))
      (node (ref "T11") (pin "E") (pinfunction "E_E") (pintype "passive"))
    )
    (net (code "69") (name "Net-(IC3B-OUT)") (class "Default")
      (node (ref "IC3") (pin "7") (pinfunction "OUT_7") (pintype "output"))
      (node (ref "T11") (pin "B") (pinfunction "B_B") (pintype "passive"))
    )
    (net (code "70") (name "Net-(IC3C--IN)") (class "Default")
      (node (ref "IC3") (pin "9") (pinfunction "-IN_9") (pintype "input"))
      (node (ref "R35") (pin "1") (pinfunction "1_1") (pintype "passive"))
      (node (ref "R37") (pin "1") (pinfunction "1_1") (pintype "passive"))
      (node (ref "T2") (pin "E") (pinfunction "E_E") (pintype "passive"))
    )
    (net (code "71") (name "Net-(IC3C-OUT)") (class "Default")
      (node (ref "IC3") (pin "8") (pinfunction "OUT_8") (pintype "output"))
      (node (ref "T2") (pin "B") (pinfunction "B_B") (pintype "passive"))
    )
    (net (code "72") (name "Net-(IC3D--IN)") (class "Default")
      (node (ref "IC3") (pin "13") (pinfunction "-IN_13") (pintype "input"))
      (node (ref "IC3") (pin "14") (pinfunction "OUT_14") (pintype "output"))
    )
    (net (code "73") (name "Net-(IC7-XTAL1)") (class "Default")
      (node (ref "C15") (pin "2") (pinfunction "2_2") (pintype "passive"))
      (node (ref "IC7") (pin "8") (pinfunction "XTAL1_8") (pintype "bidirectional"))
      (node (ref "Q1") (pin "1") (pinfunction "1_1") (pintype "passive"))
    )
    (net (code "74") (name "Net-(IC7-XTAL2)") (class "Default")
      (node (ref "C14") (pin "2") (pinfunction "2_2") (pintype "passive"))
      (node (ref "IC7") (pin "7") (pinfunction "XTAL2_7") (pintype "bidirectional"))
      (node (ref "Q1") (pin "2") (pinfunction "2_2") (pintype "passive"))
    )
    (net (code "75") (name "Net-(IC10-DTR)") (class "Default")
      (node (ref "C22") (pin "2") (pinfunction "2_2") (pintype "passive"))
      (node (ref "IC10") (pin "13") (pinfunction "DTR_13") (pintype "bidirectional"))
    )
    (net (code "76") (name "Net-(IC10-RXD)") (class "Default")
      (node (ref "IC10") (pin "3") (pinfunction "RXD_3") (pintype "bidirectional"))
      (node (ref "R18") (pin "1") (pinfunction "1_1") (pintype "passive"))
    )
    (net (code "77") (name "Net-(IC10-TXD)") (class "Default")
      (node (ref "IC10") (pin "2") (pinfunction "TXD_2") (pintype "bidirectional"))
      (node (ref "R27") (pin "1") (pinfunction "1_1") (pintype "passive"))
    )
    (net (code "78") (name "Net-(IC10-V3)") (class "Default")
      (node (ref "C16") (pin "1") (pinfunction "1_1") (pintype "passive"))
      (node (ref "IC10") (pin "4") (pinfunction "V3_4") (pintype "bidirectional"))
    )
    (net (code "79") (name "Net-(IC18-VDD)") (class "Default")
      (node (ref "C21") (pin "1") (pinfunction "1_1") (pintype "passive"))
      (node (ref "C9") (pin "1") (pinfunction "1_1") (pintype "passive"))
      (node (ref "IC18") (pin "8") (pinfunction "VDD_8") (pintype "bidirectional"))
      (node (ref "L5") (pin "1") (pinfunction "1_1") (pintype "passive"))
    )
    (net (code "80") (name "Net-(R25-Pad1)") (class "Default")
      (node (ref "R25") (pin "1") (pinfunction "1_1") (pintype "passive"))
      (node (ref "T5") (pin "B") (pinfunction "B_B") (pintype "passive"))
    )
    (net (code "81") (name "Net-(R26-Pad1)") (class "Default")
      (node (ref "R26") (pin "1") (pinfunction "1_1") (pintype "passive"))
      (node (ref "T6") (pin "B") (pinfunction "B_B") (pintype "passive"))
    )
    (net (code "82") (name "Net-(T1-G)") (class "Default")
      (node (ref "R11") (pin "2") (pinfunction "2_2") (pintype "passive"))
      (node (ref "T1") (pin "B") (pinfunction "G_B") (pintype "passive"))
    )
    (net (code "83") (name "UGND") (class "Default")
      (node (ref "AVR") (pin "GND") (pinfunction "GND_GND") (pintype "passive"))
      (node (ref "C25") (pin "2") (pinfunction "2_2") (pintype "passive"))
      (node (ref "C27") (pin "2") (pinfunction "2_2") (pintype "passive"))
      (node (ref "ESP") (pin "GND") (pinfunction "GND_GND") (pintype "passive"))
      (node (ref "R19") (pin "2") (pinfunction "2_2") (pintype "passive"))
      (node (ref "R24") (pin "2") (pinfunction "2_2") (pintype "passive"))
    )
    (net (code "84") (name "VSS") (class "Default")
      (node (ref "BR2") (pin "DC-") (pinfunction "DC-_DC-") (pintype "passive"))
      (node (ref "C1") (pin "2") (pinfunction "2_2") (pintype "passive"))
      (node (ref "C10") (pin "1") (pinfunction "1_1") (pintype "passive"))
      (node (ref "C11") (pin "1") (pinfunction "1_1") (pintype "passive"))
      (node (ref "C12") (pin "2") (pinfunction "2_2") (pintype "passive"))
      (node (ref "C13") (pin "2") (pinfunction "2_2") (pintype "passive"))
      (node (ref "C14") (pin "1") (pinfunction "1_1") (pintype "passive"))
      (node (ref "C15") (pin "1") (pinfunction "1_1") (pintype "passive"))
      (node (ref "C16") (pin "2") (pinfunction "2_2") (pintype "passive"))
      (node (ref "C17") (pin "2") (pinfunction "2_2") (pintype "passive"))
      (node (ref "C19") (pin "2") (pinfunction "2_2") (pintype "passive"))
      (node (ref "C2") (pin "2") (pinfunction "2_2") (pintype "passive"))
      (node (ref "C20") (pin "2") (pinfunction "2_2") (pintype "passive"))
      (node (ref "C21") (pin "2") (pinfunction "2_2") (pintype "passive"))
      (node (ref "C26") (pin "2") (pinfunction "2_2") (pintype "passive"))
      (node (ref "C28") (pin "2") (pinfunction "2_2") (pintype "passive"))
      (node (ref "C29") (pin "2") (pinfunction "2_2") (pintype "passive"))
      (node (ref "C3") (pin "-") (pinfunction "-_-") (pintype "passive"))
      (node (ref "C30") (pin "2") (pinfunction "2_2") (pintype "passive"))
      (node (ref "C31") (pin "2") (pinfunction "2_2") (pintype "passive"))
      (node (ref "C32") (pin "2") (pinfunction "2_2") (pintype "passive"))
      (node (ref "C33") (pin "2") (pinfunction "2_2") (pintype "passive"))
      (node (ref "C34") (pin "2") (pinfunction "2_2") (pintype "passive"))
      (node (ref "C4") (pin "2") (pinfunction "2_2") (pintype "passive"))
      (node (ref "C47") (pin "2") (pinfunction "2_2") (pintype "passive"))
      (node (ref "C48") (pin "1") (pinfunction "1_1") (pintype "passive"))
      (node (ref "C5") (pin "2") (pinfunction "2_2") (pintype "passive"))
      (node (ref "C51") (pin "2") (pinfunction "2_2") (pintype "passive"))
      (node (ref "C6") (pin "2") (pinfunction "2_2") (pintype "passive"))
      (node (ref "C7") (pin "2") (pinfunction "2_2") (pintype "passive"))
      (node (ref "C8") (pin "2") (pinfunction "2_2") (pintype "passive"))
      (node (ref "C9") (pin "2") (pinfunction "2_2") (pintype "passive"))
      (node (ref "FAN") (pin "1") (pinfunction "1_1") (pintype "passive"))
      (node (ref "IC1") (pin "4") (pinfunction "AGND_4") (pintype "power_in"))
      (node (ref "IC10") (pin "1") (pinfunction "GND_1") (pintype "power_in"))
      (node (ref "IC18") (pin "1") (pinfunction "ADDR_1") (pintype "bidirectional"))
      (node (ref "IC18") (pin "3") (pinfunction "VSS_3") (pintype "bidirectional"))
      (node (ref "IC18") (pin "5") (pinfunction "AIN1_5") (pintype "bidirectional"))
      (node (ref "IC18") (pin "7") (pinfunction "AIN3_7") (pintype "bidirectional"))
      (node (ref "IC2") (pin "1") (pinfunction "GND_1") (pintype "power_in"))
      (node (ref "IC3") (pin "11") (pinfunction "V-_11") (pintype "power_in"))
      (node (ref "IC4") (pin "2") (pinfunction "GND_2") (pintype "passive"))
      (node (ref "IC5") (pin "13") (pinfunction "GND_13") (pintype "power_in"))
      (node (ref "IC5") (pin "18") (pinfunction "GND_18") (pintype "power_in"))
      (node (ref "IC5") (pin "9") (pinfunction "GND_9") (pintype "power_in"))
      (node (ref "IC5") (pin "TP") (pinfunction "GND_TP") (pintype "power_in"))
      (node (ref "IC6") (pin "1") (pinfunction "VSS_1") (pintype "input"))
      (node (ref "IC7") (pin "18") (pinfunction "GND_18") (pintype "bidirectional"))
      (node (ref "IC7") (pin "28") (pinfunction "GND_28") (pintype "bidirectional"))
      (node (ref "IC7") (pin "39") (pinfunction "GND_39") (pintype "bidirectional"))
      (node (ref "IC7") (pin "6") (pinfunction "GND_6") (pintype "bidirectional"))
      (node (ref "IC8") (pin "1") (pinfunction "A0_1") (pintype "input"))
      (node (ref "IC8") (pin "2") (pinfunction "A1_2") (pintype "input"))
      (node (ref "IC8") (pin "3") (pinfunction "A2_3") (pintype "input"))
      (node (ref "IC8") (pin "4") (pinfunction "GND_4") (pintype "power_in"))
      (node (ref "IC8") (pin "7") (pinfunction "WP_7") (pintype "input"))
      (node (ref "IC9") (pin "2") (pinfunction "A1_2") (pintype "input"))
      (node (ref "IC9") (pin "3") (pinfunction "A2_3") (pintype "input"))
      (node (ref "IC9") (pin "4") (pinfunction "GND_4") (pintype "power_in"))
      (node (ref "IC9") (pin "7") (pinfunction "WP_7") (pintype "input"))
      (node (ref "IN") (pin "2") (pinfunction "2_2") (pintype "passive"))
      (node (ref "ISP") (pin "6") (pinfunction "6_6") (pintype "passive"))
      (node (ref "PANEL") (pin "16") (pinfunction "16_16") (pintype "passive"))
      (node (ref "PANEL") (pin "17") (pinfunction "17_17") (pintype "passive"))
      (node (ref "PANEL") (pin "18") (pinfunction "18_18") (pintype "passive"))
      (node (ref "PANEL") (pin "19") (pinfunction "19_19") (pintype "passive"))
      (node (ref "PANEL") (pin "2") (pinfunction "2_2") (pintype "passive"))
      (node (ref "PANEL") (pin "20") (pinfunction "20_20") (pintype "passive"))
      (node (ref "PRG-ESP") (pin "1") (pinfunction "1_1") (pintype "passive"))
      (node (ref "R10") (pin "1") (pinfunction "1_1") (pintype "passive"))
      (node (ref "R32") (pin "1") (pinfunction "1_1") (pintype "passive"))
      (node (ref "R35") (pin "2") (pinfunction "2_2") (pintype "passive"))
      (node (ref "R4") (pin "2") (pinfunction "2_2") (pintype "passive"))
      (node (ref "R40") (pin "2") (pinfunction "2_2") (pintype "passive"))
      (node (ref "RST-AVR") (pin "3") (pinfunction "2_3") (pintype "passive"))
      (node (ref "RST-ESP") (pin "1") (pinfunction "1_1") (pintype "passive"))
    )
    (net (code "85") (name "unconnected-(AVR-Pad+5V)") (class "Default")
      (node (ref "AVR") (pin "+5V") (pinfunction "+5V_+5V") (pintype "passive"))
    )
    (net (code "86") (name "unconnected-(HS1-Pad1)") (class "Default")
      (node (ref "HS1") (pin "1") (pinfunction "1_1") (pintype "passive"))
    )
    (net (code "87") (name "unconnected-(HS1-Pad2)") (class "Default")
      (node (ref "HS1") (pin "2") (pinfunction "2_2") (pintype "passive"))
    )
    (net (code "88") (name "unconnected-(IC2-CTS-Pad9)") (class "Default")
      (node (ref "IC2") (pin "9") (pinfunction "CTS_9") (pintype "bidirectional"))
    )
    (net (code "89") (name "unconnected-(IC2-DCD-Pad12)") (class "Default")
      (node (ref "IC2") (pin "12") (pinfunction "DCD_12") (pintype "bidirectional"))
    )
    (net (code "90") (name "unconnected-(IC2-DSR-Pad10)") (class "Default")
      (node (ref "IC2") (pin "10") (pinfunction "DSR_10") (pintype "bidirectional"))
    )
    (net (code "91") (name "unconnected-(IC2-NC1-Pad8)") (class "Default")
      (node (ref "IC2") (pin "8") (pinfunction "NC1_8") (pintype "no_connect"))
    )
    (net (code "92") (name "unconnected-(IC2-NC2-Pad7)") (class "Default")
      (node (ref "IC2") (pin "7") (pinfunction "NC2_7") (pintype "no_connect"))
    )
    (net (code "93") (name "unconnected-(IC2-R232-Pad15)") (class "Default")
      (node (ref "IC2") (pin "15") (pinfunction "R232_15") (pintype "bidirectional"))
    )
    (net (code "94") (name "unconnected-(IC2-RI-Pad11)") (class "Default")
      (node (ref "IC2") (pin "11") (pinfunction "RI_11") (pintype "bidirectional"))
    )
    (net (code "95") (name "unconnected-(IC5-ADC{slash}TOUT-Pad16)") (class "Default")
      (node (ref "IC5") (pin "16") (pinfunction "ADC/TOUT_16") (pintype "bidirectional"))
    )
    (net (code "96") (name "unconnected-(IC5-MISO{slash}IO12-Pad4)") (class "Default")
      (node (ref "IC5") (pin "4") (pinfunction "MISO/IO12_4") (pintype "bidirectional"))
    )
    (net (code "97") (name "unconnected-(IC5-MOSI{slash}IO13-Pad5)") (class "Default")
      (node (ref "IC5") (pin "5") (pinfunction "MOSI/IO13_5") (pintype "bidirectional"))
    )
    (net (code "98") (name "unconnected-(IC5-SCK{slash}IO14-Pad3)") (class "Default")
      (node (ref "IC5") (pin "3") (pinfunction "SCK/IO14_3") (pintype "bidirectional"))
    )
    (net (code "99") (name "unconnected-(IC5-WAKE{slash}IO16-Pad17)") (class "Default")
      (node (ref "IC5") (pin "17") (pinfunction "WAKE/IO16_17") (pintype "bidirectional"))
    )
    (net (code "100") (name "unconnected-(IC7-(SS{slash}OC0B{slash}PCINT12)PB4-Pad44)") (class "Default")
      (node (ref "IC7") (pin "44") (pinfunction "(SS/OC0B/PCINT12)PB4_44") (pintype "bidirectional"))
    )
    (net (code "101") (name "unconnected-(IC7-(T0{slash}XCK0O{slash}PCINT8)PB0-Pad40)") (class "Default")
      (node (ref "IC7") (pin "40") (pinfunction "(T0/XCK0O/PCINT8)PB0_40") (pintype "bidirectional"))
    )
    (net (code "102") (name "unconnected-(IC7-(TDI{slash}PCINT21)PC5-Pad24)") (class "Default")
      (node (ref "IC7") (pin "24") (pinfunction "(TDI/PCINT21)PC5_24") (pintype "bidirectional"))
    )
    (net (code "103") (name "unconnected-(IC7-(TDO{slash}PCINT20)PC4-Pad23)") (class "Default")
      (node (ref "IC7") (pin "23") (pinfunction "(TDO/PCINT20)PC4_23") (pintype "bidirectional"))
    )
    (net (code "104") (name "unconnected-(IC7-AREF-Pad29)") (class "Default")
      (node (ref "IC7") (pin "29") (pinfunction "AREF_29") (pintype "bidirectional"))
    )
    (net (code "105") (name "unconnected-(IC7-PC2(PCINT18{slash}TCK)-Pad21)") (class "Default")
      (node (ref "IC7") (pin "21") (pinfunction "PC2(PCINT18/TCK)_21") (pintype "bidirectional"))
    )
    (net (code "106") (name "unconnected-(IC7-PC3(PCINT19{slash}TMS)-Pad22)") (class "Default")
      (node (ref "IC7") (pin "22") (pinfunction "PC3(PCINT19/TMS)_22") (pintype "bidirectional"))
    )
    (net (code "107") (name "unconnected-(IC7-PD4(PCINT28{slash}XCK1{slash}OC1B)-Pad13)") (class "Default")
      (node (ref "IC7") (pin "13") (pinfunction "PD4(PCINT28/XCK1/OC1B)_13") (pintype "bidirectional"))
    )
    (net (code "108") (name "unconnected-(IC7-PD5(PCINT29{slash}OC1A)-Pad14)") (class "Default")
      (node (ref "IC7") (pin "14") (pinfunction "PD5(PCINT29/OC1A)_14") (pintype "bidirectional"))
    )
    (net (code "109") (name "unconnected-(IC7-PD6(PCINT30{slash}OC2B{slash}ICP)-Pad15)") (class "Default")
      (node (ref "IC7") (pin "15") (pinfunction "PD6(PCINT30/OC2B/ICP)_15") (pintype "bidirectional"))
    )
    (net (code "110") (name "unconnected-(IC7-PD7(PCINT31{slash}OC2A)-Pad16)") (class "Default")
      (node (ref "IC7") (pin "16") (pinfunction "PD7(PCINT31/OC2A)_16") (pintype "bidirectional"))
    )
    (net (code "111") (name "unconnected-(IC10-CTS-Pad9)") (class "Default")
      (node (ref "IC10") (pin "9") (pinfunction "CTS_9") (pintype "bidirectional"))
    )
    (net (code "112") (name "unconnected-(IC10-DCD-Pad12)") (class "Default")
      (node (ref "IC10") (pin "12") (pinfunction "DCD_12") (pintype "bidirectional"))
    )
    (net (code "113") (name "unconnected-(IC10-DSR-Pad10)") (class "Default")
      (node (ref "IC10") (pin "10") (pinfunction "DSR_10") (pintype "bidirectional"))
    )
    (net (code "114") (name "unconnected-(IC10-NC1-Pad8)") (class "Default")
      (node (ref "IC10") (pin "8") (pinfunction "NC1_8") (pintype "no_connect"))
    )
    (net (code "115") (name "unconnected-(IC10-NC2-Pad7)") (class "Default")
      (node (ref "IC10") (pin "7") (pinfunction "NC2_7") (pintype "no_connect"))
    )
    (net (code "116") (name "unconnected-(IC10-R232-Pad15)") (class "Default")
      (node (ref "IC10") (pin "15") (pinfunction "R232_15") (pintype "bidirectional"))
    )
    (net (code "117") (name "unconnected-(IC10-RI-Pad11)") (class "Default")
      (node (ref "IC10") (pin "11") (pinfunction "RI_11") (pintype "bidirectional"))
    )
    (net (code "118") (name "unconnected-(IC10-RTS-Pad14)") (class "Default")
      (node (ref "IC10") (pin "14") (pinfunction "RTS_14") (pintype "bidirectional"))
    )
    (net (code "119") (name "unconnected-(IC18-ALERT{slash}RDY-Pad2)") (class "Default")
      (node (ref "IC18") (pin "2") (pinfunction "ALERT/RDY_2") (pintype "bidirectional"))
    )
    (net (code "120") (name "unconnected-(ISP-Pad2)") (class "Default")
      (node (ref "ISP") (pin "2") (pinfunction "2_2") (pintype "passive"))
    )
  )
)
